# main.net
KiCad netlist of a schematic drawn in EAGLE
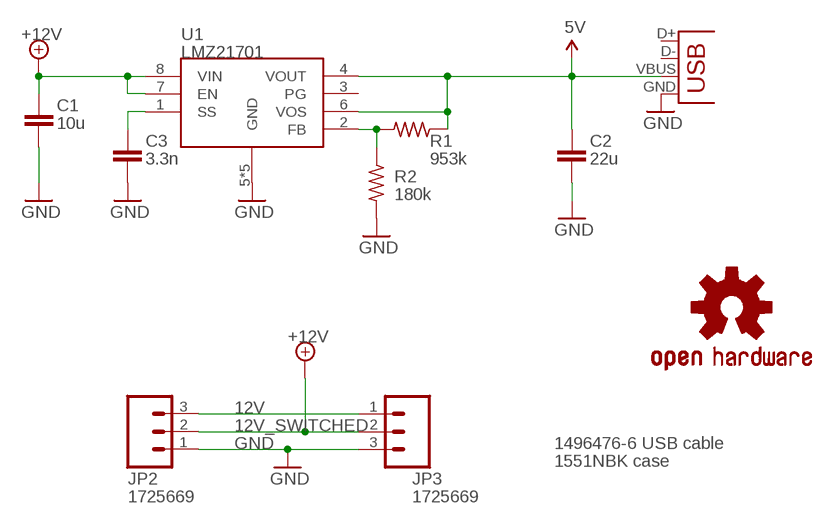
[diagram p0: schematic, sheet 1]

(export (version "E")
  (design (tool "Eeschema 10.0.6"))
  (components
    (comp (ref "C1")
      (value "10u")
      (footprint "eagle-import:C1206")
      (libsource (lib "eagle-import") (part "C-EUC1206"))
    )
    (comp (ref "C2")
      (value "22u")
      (footprint "eagle-import:C1206")
      (libsource (lib "eagle-import") (part "C-EUC1206"))
    )
    (comp (ref "C3")
      (value "3.3n")
      (footprint "eagle-import:C0603")
      (libsource (lib "eagle-import") (part "C-EUC0603"))
    )
    (comp (ref "JP1")
      (value "62900416021")
      (footprint "eagle-import:USB-A-S-SILK-FEMALE")
      (libsource (lib "eagle-import") (part "USB_"))
    )
    (comp (ref "JP2")
      (value "1725669")
      (footprint "eagle-import:1X03")
      (libsource (lib "eagle-import") (part "M03PTH"))
    )
    (comp (ref "JP3")
      (value "1725669")
      (footprint "eagle-import:1X03")
      (libsource (lib "eagle-import") (part "M03PTH"))
    )
    (comp (ref "LOGO1")
      (value "OSHW-LOGOL")
      (footprint "eagle-import:OSHW-LOGO-L")
      (libsource (lib "eagle-import") (part "OSHW-LOGOL"))
    )
    (comp (ref "R1")
      (value "953k")
      (footprint "eagle-import:R0603")
      (libsource (lib "eagle-import") (part "R-US_R0603"))
    )
    (comp (ref "R2")
      (value "180k")
      (footprint "eagle-import:R0603")
      (libsource (lib "eagle-import") (part "R-US_R0603"))
    )
    (comp (ref "U1")
      (value "LMZ21701")
      (footprint "eagle-import:LMZ21701")
      (libsource (lib "eagle-import") (part "LMZ21701"))
    )
  )
  (nets
    (net (code "1") (name "+12V") (class "Default")
      (node (ref "C1") (pin "1") (pinfunction "1_1") (pintype "passive"))
      (node (ref "JP2") (pin "2") (pinfunction "2_2") (pintype "passive"))
      (node (ref "JP3") (pin "2") (pinfunction "2_2") (pintype "passive"))
      (node (ref "U1") (pin "7") (pinfunction "EN_7") (pintype "bidirectional"))
      (node (ref "U1") (pin "8") (pinfunction "VIN_8") (pintype "bidirectional"))
    )
    (net (code "2") (name "/12V") (class "Default")
      (node (ref "JP2") (pin "3") (pinfunction "3_3") (pintype "passive"))
      (node (ref "JP3") (pin "1") (pinfunction "1_1") (pintype "passive"))
    )
    (net (code "3") (name "5V") (class "Default")
      (node (ref "C2") (pin "1") (pinfunction "1_1") (pintype "passive"))
      (node (ref "JP1") (pin "VBUS") (pinfunction "VBUS_VBUS") (pintype "bidirectional"))
      (node (ref "R1") (pin "1") (pinfunction "1_1") (pintype "passive"))
      (node (ref "U1") (pin "4") (pinfunction "VOUT_4") (pintype "bidirectional"))
      (node (ref "U1") (pin "6") (pinfunction "VOS_6") (pintype "bidirectional"))
    )
    (net (code "4") (name "GND") (class "Default")
      (node (ref "C1") (pin "2") (pinfunction "2_2") (pintype "passive"))
      (node (ref "C2") (pin "2") (pinfunction "2_2") (pintype "passive"))
      (node (ref "C3") (pin "2") (pinfunction "2_2") (pintype "passive"))
      (node (ref "JP1") (pin "GND") (pinfunction "GND_GND") (pintype "bidirectional"))
      (node (ref "JP2") (pin "1") (pinfunction "1_1") (pintype "passive"))
      (node (ref "JP3") (pin "3") (pinfunction "3_3") (pintype "passive"))
      (node (ref "R2") (pin "2") (pinfunction "2_2") (pintype "passive"))
      (node (ref "U1") (pin "5") (pinfunction "GND_5") (pintype "bidirectional"))
      (node (ref "U1") (pin "G1") (pinfunction "GND_G1") (pintype "bidirectional"))
      (node (ref "U1") (pin "G1V") (pinfunction "GND_G1V") (pintype "bidirectional"))
      (node (ref "U1") (pin "G2") (pinfunction "GND_G2") (pintype "bidirectional"))
      (node (ref "U1") (pin "G2V") (pinfunction "GND_G2V") (pintype "bidirectional"))
    )
    (net (code "5") (name "Net-(U1-FB)") (class "Default")
      (node (ref "R1") (pin "2") (pinfunction "2_2") (pintype "passive"))
      (node (ref "R2") (pin "1") (pinfunction "1_1") (pintype "passive"))
      (node (ref "U1") (pin "2") (pinfunction "FB_2") (pintype "bidirectional"))
    )
    (net (code "6") (name "Net-(U1-SS)") (class "Default")
      (node (ref "C3") (pin "1") (pinfunction "1_1") (pintype "passive"))
      (node (ref "U1") (pin "1") (pinfunction "SS_1") (pintype "bidirectional"))
    )
    (net (code "7") (name "unconnected-(JP1-PadD+)") (class "Default")
      (node (ref "JP1") (pin "D+") (pinfunction "D+_D+") (pintype "bidirectional"))
    )
    (net (code "8") (name "unconnected-(JP1-PadD-)") (class "Default")
      (node (ref "JP1") (pin "D-") (pinfunction "D-_D-") (pintype "bidirectional"))
    )
    (net (code "9") (name "unconnected-(U1-PG-Pad3)") (class "Default")
      (node (ref "U1") (pin "3") (pinfunction "PG_3") (pintype "bidirectional"))
    )
  )
)
